# VirtualWire.net
KiCad netlist of a schematic drawn in Altium Designer
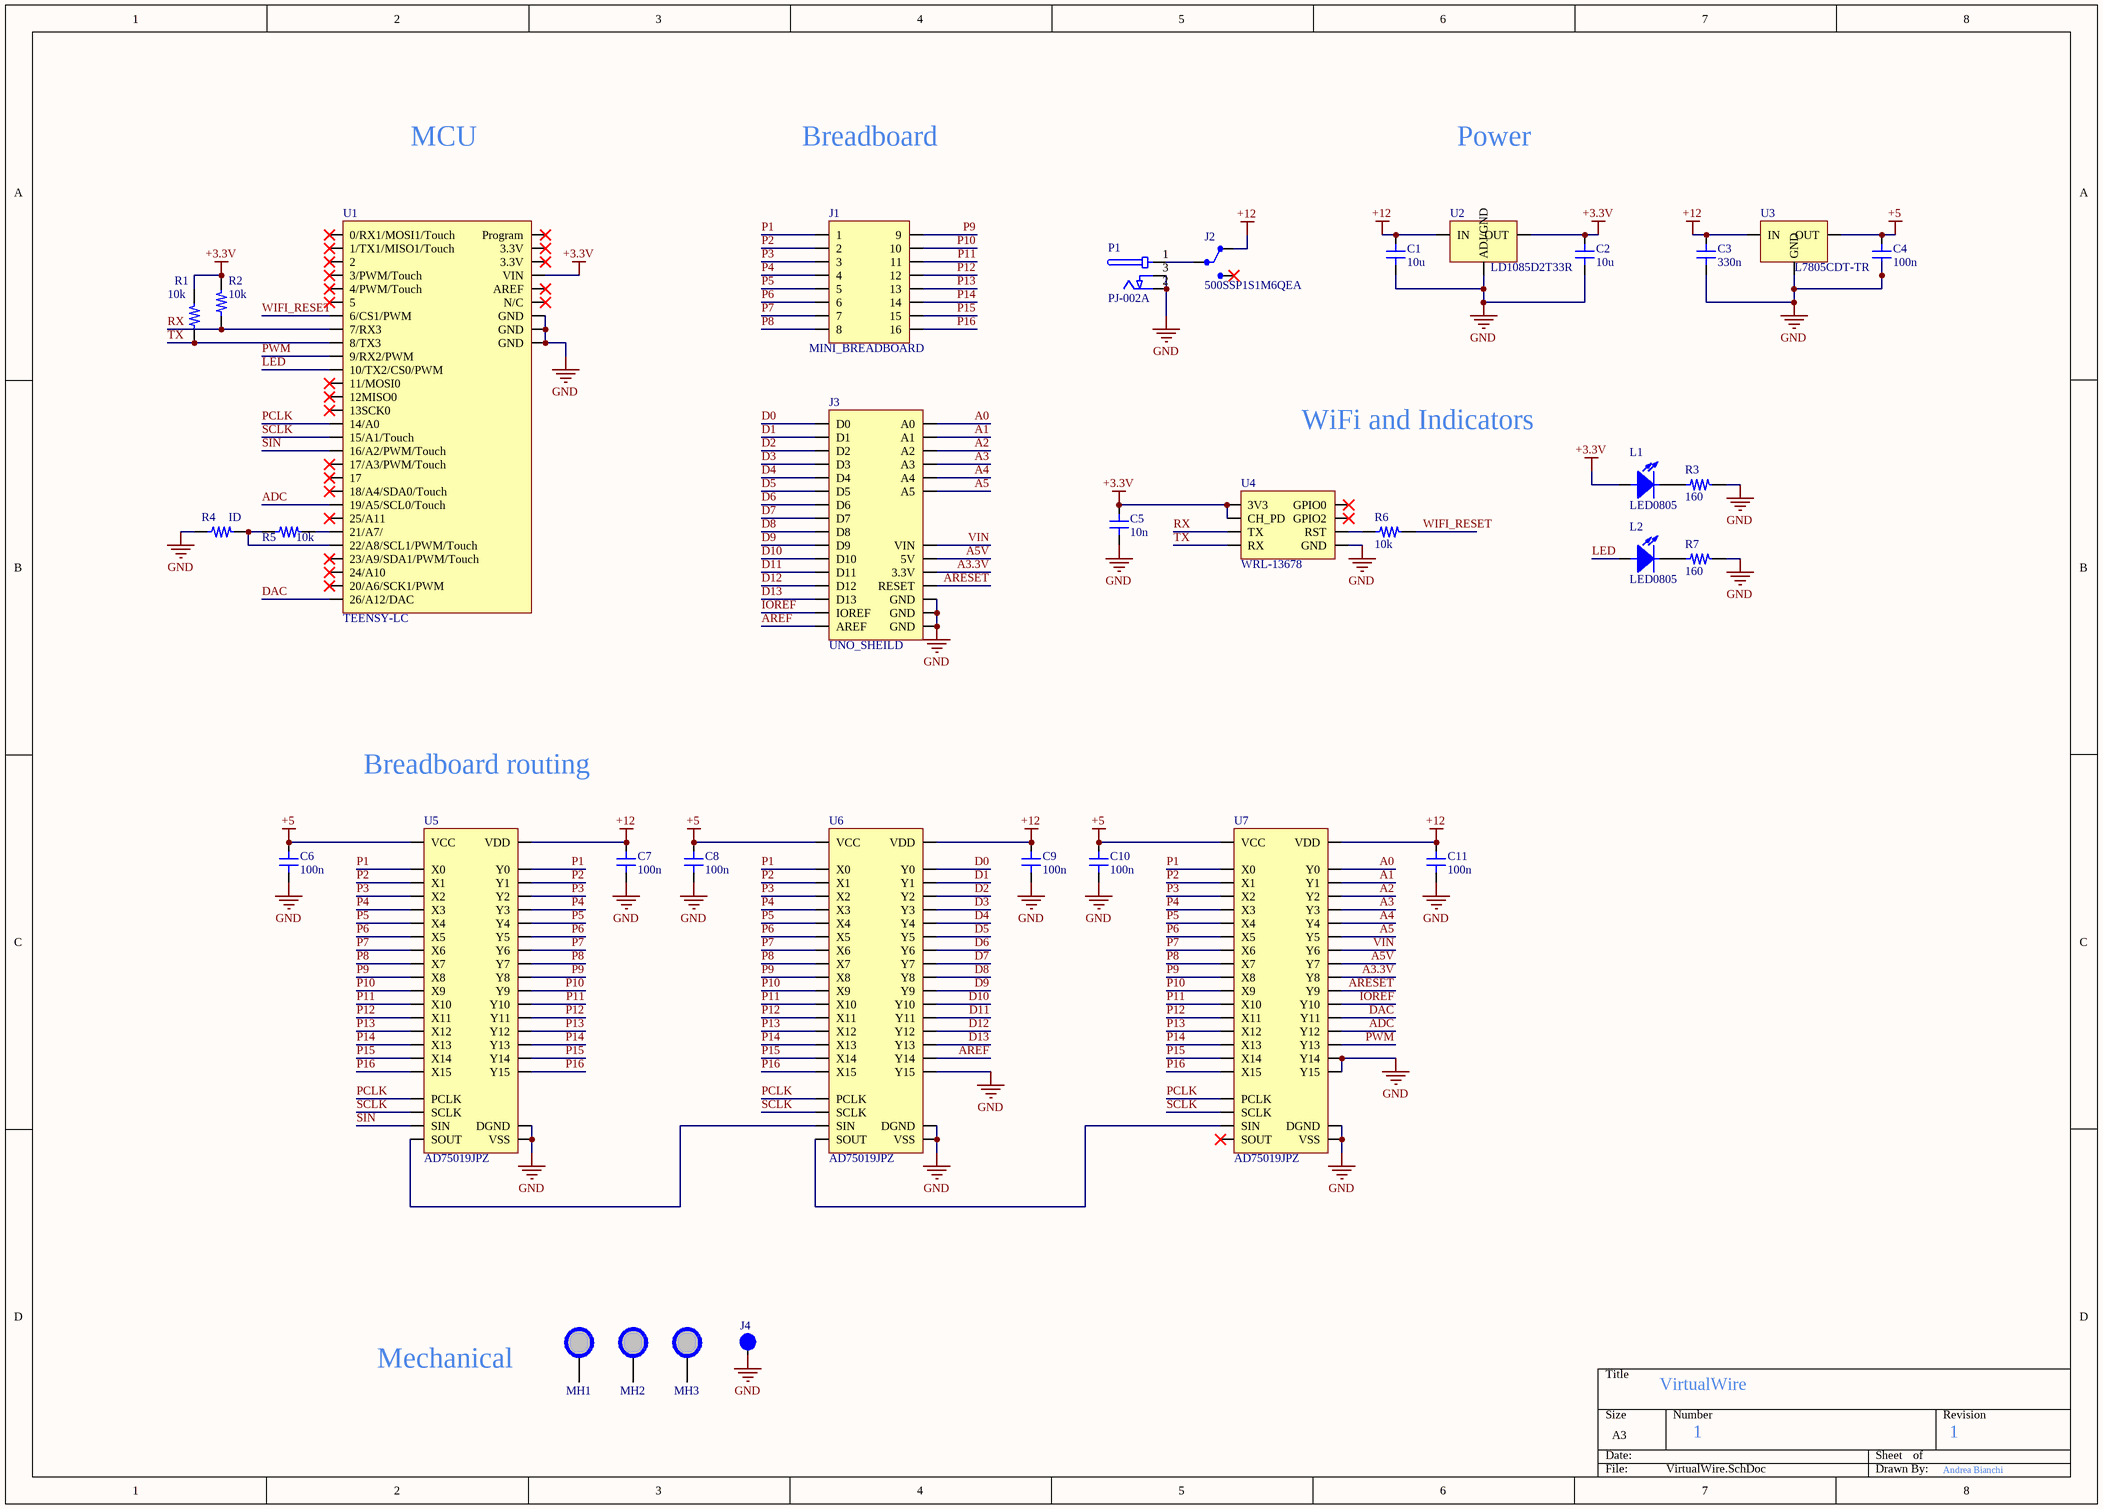
[diagram p0: VirtualWire.SchDoc]

(export (version "E")
  (design (tool "Eeschema 10.0.6"))
  (components
    (comp (ref "C1")
      (value "10u")
      (footprint "C0805")
      (description "10uF")
      (libsource (lib "VirtualWire") (part "C805_10u"))
    )
    (comp (ref "C2")
      (value "10u")
      (footprint "C0805")
      (description "10uF")
      (libsource (lib "VirtualWire") (part "C805_10u"))
    )
    (comp (ref "C3")
      (value "330n")
      (footprint "C0805")
      (description "330nF")
      (libsource (lib "VirtualWire") (part "C805_330n"))
    )
    (comp (ref "C4")
      (value "100n")
      (footprint "C0805")
      (description "100nF")
      (libsource (lib "VirtualWire") (part "C805_100n"))
    )
    (comp (ref "C5")
      (value "10n")
      (footprint "C0805")
      (description "10nF")
      (libsource (lib "VirtualWire") (part "C805_10n"))
    )
    (comp (ref "C6")
      (value "100n")
      (footprint "C0805")
      (description "100nF")
      (libsource (lib "VirtualWire") (part "C805_100n"))
    )
    (comp (ref "C7")
      (value "100n")
      (footprint "C0805")
      (description "100nF")
      (libsource (lib "VirtualWire") (part "C805_100n"))
    )
    (comp (ref "C8")
      (value "100n")
      (footprint "C0805")
      (description "100nF")
      (libsource (lib "VirtualWire") (part "C805_100n"))
    )
    (comp (ref "C9")
      (value "100n")
      (footprint "C0805")
      (description "100nF")
      (libsource (lib "VirtualWire") (part "C805_100n"))
    )
    (comp (ref "C10")
      (value "100n")
      (footprint "C0805")
      (description "100nF")
      (libsource (lib "VirtualWire") (part "C805_100n"))
    )
    (comp (ref "C11")
      (value "100n")
      (footprint "C0805")
      (description "100nF")
      (libsource (lib "VirtualWire") (part "C805_100n"))
    )
    (comp (ref "J1")
      (value "MINI_BREADBOARD")
      (footprint "MINI_BREADBOARD HOLE")
      (description "Mini Breadboard 16x2")
      (libsource (lib "VirtualWire") (part "MINI_BREADBOARD"))
    )
    (comp (ref "J2")
      (value "500SSP1S1M6QEA")
      (footprint "SLIDE SPDT")
      (description "SWITCH SLIDE SPDT 5A 120V")
      (fields (field (name "MANUFACTURER") "E-Switch"))
      (libsource (lib "VirtualWire") (part "SLIDE SPDT"))
    )
    (comp (ref "J3")
      (value "UNO_SHEILD")
      (footprint "ARDUINO_UNO_SHIELD")
      (libsource (lib "VirtualWire") (part "ARDUINO_UNO_SHIELD"))
    )
    (comp (ref "J4")
      (value "EPAD")
      (footprint "EPAD")
      (description "Exposed PAD")
      (libsource (lib "VirtualWire") (part "EPAD"))
    )
    (comp (ref "L1")
      (value "LED0805")
      (footprint "LED0805")
      (description "LED0805 any color")
      (libsource (lib "VirtualWire") (part "LED0805"))
    )
    (comp (ref "L2")
      (value "LED0805")
      (footprint "LED0805")
      (description "LED0805 any color")
      (libsource (lib "VirtualWire") (part "LED0805"))
    )
    (comp (ref "MH1")
      (value "MH 3.2mm NP")
      (footprint "MH3.2mm")
      (description "Mounting hole 3.2mm non plated")
      (libsource (lib "VirtualWire") (part "MHNP"))
    )
    (comp (ref "MH2")
      (value "MH 3.2mm NP")
      (footprint "MH3.2mm")
      (description "Mounting hole 3.2mm non plated")
      (libsource (lib "VirtualWire") (part "MHNP"))
    )
    (comp (ref "MH3")
      (value "MH 3.2mm NP")
      (footprint "MH3.2mm")
      (description "Mounting hole 3.2mm non plated")
      (libsource (lib "VirtualWire") (part "MHNP"))
    )
    (comp (ref "P1")
      (value "PJ-002A")
      (footprint "PJ-002A")
      (description "PJ-002 Series 2 x 6.5 mm 16 V Right Angle Through Hole Power Jack")
      (fields (field (name "MANUFACTURER") "CUI"))
      (libsource (lib "VirtualWire") (part "PJ-002A"))
    )
    (comp (ref "R1") (value "10k") (footprint "R0805") (libsource (lib "VirtualWire") (part "R0805_10k")))
    (comp (ref "R2") (value "10k") (footprint "R0805") (libsource (lib "VirtualWire") (part "R0805_10k")))
    (comp (ref "R3")
      (value "160")
      (footprint "R0805")
      (description "160 Ohm")
      (libsource (lib "VirtualWire") (part "R0805_160"))
    )
    (comp (ref "R4") (value "ID") (footprint "R0805") (libsource (lib "VirtualWire") (part "R0805_10k")))
    (comp (ref "R5") (value "10k") (footprint "R0805") (libsource (lib "VirtualWire") (part "R0805_10k")))
    (comp (ref "R6") (value "10k") (footprint "R0805") (libsource (lib "VirtualWire") (part "R0805_10k")))
    (comp (ref "R7")
      (value "160")
      (footprint "R0805")
      (description "160 Ohm")
      (libsource (lib "VirtualWire") (part "R0805_160"))
    )
    (comp (ref "U1")
      (value "TEENSY-LC")
      (footprint "TEENSY-LC")
      (description "DEV TEENSY LC 13305")
      (fields (field (name "MANUFACTURER") "SparkFun") (field (name "MANUFACTURER PART NUMBER") "DEV-13305"))
      (libsource (lib "VirtualWire") (part "TEENSY-LC"))
    )
    (comp (ref "U2")
      (value "LD1085D2T33R")
      (footprint "D2PAK")
      (description "Fixed LDO Voltage Regulator, 6.3V to 30V, 1.3V Dropout, 3.3Vout, 3Aout, TO-263-3")
      (fields (field (name "MANUFACTURER") "STMicroelectronics"))
      (libsource (lib "VirtualWire") (part "LD1085D2T33R"))
    )
    (comp (ref "U3")
      (value "L7805CDT-TR")
      (footprint "DPAK")
      (description "IC REG LDO 5V 1.5A DPAK")
      (fields (field (name "MANUFACTURER") "STMicroelectronics"))
      (libsource (lib "VirtualWire") (part "L7805CDT-TR"))
    )
    (comp (ref "U4")
      (value "WRL-13678")
      (footprint "ESP8266")
      (description "WIFI ESP8266 MOD WIFI TRACE ANT")
      (fields (field (name "MANUFACTURER") "SparkFun"))
      (libsource (lib "VirtualWire") (part "ESP8266"))
    )
    (comp (ref "U5")
      (value "AD75019JPZ")
      (footprint "PLCC44_DIP")
      (description "SWITCH CROSSPOINT 16X16, SMD, 75019")
      (fields (field (name "MANUFACTURER") "Analog Devices"))
      (libsource (lib "VirtualWire") (part "AD75019JPZ"))
    )
    (comp (ref "U6")
      (value "AD75019JPZ")
      (footprint "PLCC44_DIP")
      (description "SWITCH CROSSPOINT 16X16, SMD, 75019")
      (fields (field (name "MANUFACTURER") "Analog Devices"))
      (libsource (lib "VirtualWire") (part "AD75019JPZ"))
    )
    (comp (ref "U7")
      (value "AD75019JPZ")
      (footprint "PLCC44_DIP")
      (description "SWITCH CROSSPOINT 16X16, SMD, 75019")
      (fields (field (name "MANUFACTURER") "Analog Devices"))
      (libsource (lib "VirtualWire") (part "AD75019JPZ"))
    )
  )
  (nets
    (net (code "1") (name "+3.3V") (class "Default")
      (node (ref "C2") (pin "2") (pinfunction "2_2") (pintype "passive"))
      (node (ref "C5") (pin "2") (pinfunction "2_2") (pintype "passive"))
      (node (ref "L1") (pin "2") (pinfunction "A_2") (pintype "passive"))
      (node (ref "R1") (pin "2") (pinfunction "2_2") (pintype "passive"))
      (node (ref "R2") (pin "2") (pinfunction "2_2") (pintype "passive"))
      (node (ref "U1") (pin "33") (pinfunction "VIN_33") (pintype "passive"))
      (node (ref "U2") (pin "4") (pinfunction "OUT_4") (pintype "passive"))
      (node (ref "U4") (pin "2") (pinfunction "CH_PD_2") (pintype "passive"))
      (node (ref "U4") (pin "4") (pinfunction "3V3_4") (pintype "passive"))
    )
    (net (code "2") (name "+5") (class "Default")
      (node (ref "C10") (pin "2") (pinfunction "2_2") (pintype "passive"))
      (node (ref "C4") (pin "2") (pinfunction "2_2") (pintype "passive"))
      (node (ref "C6") (pin "2") (pinfunction "2_2") (pintype "passive"))
      (node (ref "C8") (pin "2") (pinfunction "2_2") (pintype "passive"))
      (node (ref "U3") (pin "3") (pinfunction "OUT_3") (pintype "passive"))
      (node (ref "U5") (pin "42") (pinfunction "VCC_42") (pintype "passive"))
      (node (ref "U6") (pin "42") (pinfunction "VCC_42") (pintype "passive"))
      (node (ref "U7") (pin "42") (pinfunction "VCC_42") (pintype "passive"))
    )
    (net (code "3") (name "+12") (class "Default")
      (node (ref "C1") (pin "2") (pinfunction "2_2") (pintype "passive"))
      (node (ref "C11") (pin "2") (pinfunction "2_2") (pintype "passive"))
      (node (ref "C3") (pin "2") (pinfunction "2_2") (pintype "passive"))
      (node (ref "C7") (pin "2") (pinfunction "2_2") (pintype "passive"))
      (node (ref "C9") (pin "2") (pinfunction "2_2") (pintype "passive"))
      (node (ref "J2") (pin "1") (pinfunction "1_1") (pintype "passive"))
      (node (ref "U2") (pin "3") (pinfunction "IN_3") (pintype "passive"))
      (node (ref "U3") (pin "1") (pinfunction "IN_1") (pintype "passive"))
      (node (ref "U5") (pin "41") (pinfunction "VDD_41") (pintype "passive"))
      (node (ref "U6") (pin "41") (pinfunction "VDD_41") (pintype "passive"))
      (node (ref "U7") (pin "41") (pinfunction "VDD_41") (pintype "passive"))
    )
    (net (code "4") (name "/A0") (class "Default")
      (node (ref "J3") (pin "22") (pinfunction "A0_22") (pintype "passive"))
      (node (ref "U7") (pin "31") (pinfunction "Y0_31") (pintype "passive"))
    )
    (net (code "5") (name "/A1") (class "Default")
      (node (ref "J3") (pin "21") (pinfunction "A1_21") (pintype "passive"))
      (node (ref "U7") (pin "32") (pinfunction "Y1_32") (pintype "passive"))
    )
    (net (code "6") (name "/A2") (class "Default")
      (node (ref "J3") (pin "20") (pinfunction "A2_20") (pintype "passive"))
      (node (ref "U7") (pin "33") (pinfunction "Y2_33") (pintype "passive"))
    )
    (net (code "7") (name "/A3") (class "Default")
      (node (ref "J3") (pin "19") (pinfunction "A3_19") (pintype "passive"))
      (node (ref "U7") (pin "34") (pinfunction "Y3_34") (pintype "passive"))
    )
    (net (code "8") (name "/A3.3V") (class "Default")
      (node (ref "J3") (pin "27") (pinfunction "3.3V_27") (pintype "passive"))
      (node (ref "U7") (pin "14") (pinfunction "Y8_14") (pintype "passive"))
    )
    (net (code "9") (name "/A4") (class "Default")
      (node (ref "J3") (pin "18") (pinfunction "A4_18") (pintype "passive"))
      (node (ref "U7") (pin "35") (pinfunction "Y4_35") (pintype "passive"))
    )
    (net (code "10") (name "/A5") (class "Default")
      (node (ref "J3") (pin "17") (pinfunction "A5_17") (pintype "passive"))
      (node (ref "U7") (pin "36") (pinfunction "Y5_36") (pintype "passive"))
    )
    (net (code "11") (name "/A5V") (class "Default")
      (node (ref "J3") (pin "26") (pinfunction "5V_26") (pintype "passive"))
      (node (ref "U7") (pin "38") (pinfunction "Y7_38") (pintype "passive"))
    )
    (net (code "12") (name "/ADC") (class "Default")
      (node (ref "U1") (pin "26") (pinfunction "19/A5/SCL0/Touch_26") (pintype "passive"))
      (node (ref "U7") (pin "10") (pinfunction "Y12_10") (pintype "passive"))
    )
    (net (code "13") (name "/AREF") (class "Default")
      (node (ref "J3") (pin "16") (pinfunction "AREF_16") (pintype "passive"))
      (node (ref "U6") (pin "8") (pinfunction "Y14_8") (pintype "passive"))
    )
    (net (code "14") (name "/ARESET") (class "Default")
      (node (ref "J3") (pin "28") (pinfunction "RESET_28") (pintype "passive"))
      (node (ref "U7") (pin "13") (pinfunction "Y9_13") (pintype "passive"))
    )
    (net (code "15") (name "/D0") (class "Default")
      (node (ref "J3") (pin "1") (pinfunction "D0_1") (pintype "passive"))
      (node (ref "U6") (pin "31") (pinfunction "Y0_31") (pintype "passive"))
    )
    (net (code "16") (name "/D1") (class "Default")
      (node (ref "J3") (pin "2") (pinfunction "D1_2") (pintype "passive"))
      (node (ref "U6") (pin "32") (pinfunction "Y1_32") (pintype "passive"))
    )
    (net (code "17") (name "/D2") (class "Default")
      (node (ref "J3") (pin "3") (pinfunction "D2_3") (pintype "passive"))
      (node (ref "U6") (pin "33") (pinfunction "Y2_33") (pintype "passive"))
    )
    (net (code "18") (name "/D3") (class "Default")
      (node (ref "J3") (pin "4") (pinfunction "D3_4") (pintype "passive"))
      (node (ref "U6") (pin "34") (pinfunction "Y3_34") (pintype "passive"))
    )
    (net (code "19") (name "/D4") (class "Default")
      (node (ref "J3") (pin "5") (pinfunction "D4_5") (pintype "passive"))
      (node (ref "U6") (pin "35") (pinfunction "Y4_35") (pintype "passive"))
    )
    (net (code "20") (name "/D5") (class "Default")
      (node (ref "J3") (pin "6") (pinfunction "D5_6") (pintype "passive"))
      (node (ref "U6") (pin "36") (pinfunction "Y5_36") (pintype "passive"))
    )
    (net (code "21") (name "/D6") (class "Default")
      (node (ref "J3") (pin "7") (pinfunction "D6_7") (pintype "passive"))
      (node (ref "U6") (pin "37") (pinfunction "Y6_37") (pintype "passive"))
    )
    (net (code "22") (name "/D7") (class "Default")
      (node (ref "J3") (pin "8") (pinfunction "D7_8") (pintype "passive"))
      (node (ref "U6") (pin "38") (pinfunction "Y7_38") (pintype "passive"))
    )
    (net (code "23") (name "/D8") (class "Default")
      (node (ref "J3") (pin "9") (pinfunction "D8_9") (pintype "passive"))
      (node (ref "U6") (pin "14") (pinfunction "Y8_14") (pintype "passive"))
    )
    (net (code "24") (name "/D9") (class "Default")
      (node (ref "J3") (pin "10") (pinfunction "D9_10") (pintype "passive"))
      (node (ref "U6") (pin "13") (pinfunction "Y9_13") (pintype "passive"))
    )
    (net (code "25") (name "/D10") (class "Default")
      (node (ref "J3") (pin "11") (pinfunction "D10_11") (pintype "passive"))
      (node (ref "U6") (pin "12") (pinfunction "Y10_12") (pintype "passive"))
    )
    (net (code "26") (name "/D11") (class "Default")
      (node (ref "J3") (pin "12") (pinfunction "D11_12") (pintype "passive"))
      (node (ref "U6") (pin "11") (pinfunction "Y11_11") (pintype "passive"))
    )
    (net (code "27") (name "/D12") (class "Default")
      (node (ref "J3") (pin "13") (pinfunction "D12_13") (pintype "passive"))
      (node (ref "U6") (pin "10") (pinfunction "Y12_10") (pintype "passive"))
    )
    (net (code "28") (name "/D13") (class "Default")
      (node (ref "J3") (pin "14") (pinfunction "D13_14") (pintype "passive"))
      (node (ref "U6") (pin "9") (pinfunction "Y13_9") (pintype "passive"))
    )
    (net (code "29") (name "/DAC") (class "Default")
      (node (ref "U1") (pin "19") (pinfunction "26/A12/DAC_19") (pintype "passive"))
      (node (ref "U7") (pin "11") (pinfunction "Y11_11") (pintype "passive"))
    )
    (net (code "30") (name "/IOREF") (class "Default")
      (node (ref "J3") (pin "29") (pinfunction "IOREF_29") (pintype "passive"))
      (node (ref "U7") (pin "12") (pinfunction "Y10_12") (pintype "passive"))
    )
    (net (code "31") (name "/LED") (class "Default")
      (node (ref "L2") (pin "2") (pinfunction "A_2") (pintype "passive"))
      (node (ref "U1") (pin "12") (pinfunction "10/TX2/CS0/PWM_12") (pintype "passive"))
    )
    (net (code "32") (name "/P1") (class "Default")
      (node (ref "J1") (pin "1") (pinfunction "1_1") (pintype "passive"))
      (node (ref "U5") (pin "15") (pinfunction "X0_15") (pintype "passive"))
      (node (ref "U5") (pin "31") (pinfunction "Y0_31") (pintype "passive"))
      (node (ref "U6") (pin "15") (pinfunction "X0_15") (pintype "passive"))
      (node (ref "U7") (pin "15") (pinfunction "X0_15") (pintype "passive"))
    )
    (net (code "33") (name "/P2") (class "Default")
      (node (ref "J1") (pin "2") (pinfunction "2_2") (pintype "passive"))
      (node (ref "U5") (pin "16") (pinfunction "X1_16") (pintype "passive"))
      (node (ref "U5") (pin "32") (pinfunction "Y1_32") (pintype "passive"))
      (node (ref "U6") (pin "16") (pinfunction "X1_16") (pintype "passive"))
      (node (ref "U7") (pin "16") (pinfunction "X1_16") (pintype "passive"))
    )
    (net (code "34") (name "/P3") (class "Default")
      (node (ref "J1") (pin "3") (pinfunction "3_3") (pintype "passive"))
      (node (ref "U5") (pin "17") (pinfunction "X2_17") (pintype "passive"))
      (node (ref "U5") (pin "33") (pinfunction "Y2_33") (pintype "passive"))
      (node (ref "U6") (pin "17") (pinfunction "X2_17") (pintype "passive"))
      (node (ref "U7") (pin "17") (pinfunction "X2_17") (pintype "passive"))
    )
    (net (code "35") (name "/P4") (class "Default")
      (node (ref "J1") (pin "4") (pinfunction "4_4") (pintype "passive"))
      (node (ref "U5") (pin "18") (pinfunction "X3_18") (pintype "passive"))
      (node (ref "U5") (pin "34") (pinfunction "Y3_34") (pintype "passive"))
      (node (ref "U6") (pin "18") (pinfunction "X3_18") (pintype "passive"))
      (node (ref "U7") (pin "18") (pinfunction "X3_18") (pintype "passive"))
    )
    (net (code "36") (name "/P5") (class "Default")
      (node (ref "J1") (pin "5") (pinfunction "5_5") (pintype "passive"))
      (node (ref "U5") (pin "19") (pinfunction "X4_19") (pintype "passive"))
      (node (ref "U5") (pin "35") (pinfunction "Y4_35") (pintype "passive"))
      (node (ref "U6") (pin "19") (pinfunction "X4_19") (pintype "passive"))
      (node (ref "U7") (pin "19") (pinfunction "X4_19") (pintype "passive"))
    )
    (net (code "37") (name "/P6") (class "Default")
      (node (ref "J1") (pin "6") (pinfunction "6_6") (pintype "passive"))
      (node (ref "U5") (pin "20") (pinfunction "X5_20") (pintype "passive"))
      (node (ref "U5") (pin "36") (pinfunction "Y5_36") (pintype "passive"))
      (node (ref "U6") (pin "20") (pinfunction "X5_20") (pintype "passive"))
      (node (ref "U7") (pin "20") (pinfunction "X5_20") (pintype "passive"))
    )
    (net (code "38") (name "/P7") (class "Default")
      (node (ref "J1") (pin "7") (pinfunction "7_7") (pintype "passive"))
      (node (ref "U5") (pin "21") (pinfunction "X6_21") (pintype "passive"))
      (node (ref "U5") (pin "37") (pinfunction "Y6_37") (pintype "passive"))
      (node (ref "U6") (pin "21") (pinfunction "X6_21") (pintype "passive"))
      (node (ref "U7") (pin "21") (pinfunction "X6_21") (pintype "passive"))
    )
    (net (code "39") (name "/P8") (class "Default")
      (node (ref "J1") (pin "8") (pinfunction "8_8") (pintype "passive"))
      (node (ref "U5") (pin "22") (pinfunction "X7_22") (pintype "passive"))
      (node (ref "U5") (pin "38") (pinfunction "Y7_38") (pintype "passive"))
      (node (ref "U6") (pin "22") (pinfunction "X7_22") (pintype "passive"))
      (node (ref "U7") (pin "22") (pinfunction "X7_22") (pintype "passive"))
    )
    (net (code "40") (name "/P9") (class "Default")
      (node (ref "J1") (pin "9") (pinfunction "9_9") (pintype "passive"))
      (node (ref "U5") (pin "14") (pinfunction "Y8_14") (pintype "passive"))
      (node (ref "U5") (pin "23") (pinfunction "X8_23") (pintype "passive"))
      (node (ref "U6") (pin "23") (pinfunction "X8_23") (pintype "passive"))
      (node (ref "U7") (pin "23") (pinfunction "X8_23") (pintype "passive"))
    )
    (net (code "41") (name "/P10") (class "Default")
      (node (ref "J1") (pin "10") (pinfunction "10_10") (pintype "passive"))
      (node (ref "U5") (pin "13") (pinfunction "Y9_13") (pintype "passive"))
      (node (ref "U5") (pin "24") (pinfunction "X9_24") (pintype "passive"))
      (node (ref "U6") (pin "24") (pinfunction "X9_24") (pintype "passive"))
      (node (ref "U7") (pin "24") (pinfunction "X9_24") (pintype "passive"))
    )
    (net (code "42") (name "/P11") (class "Default")
      (node (ref "J1") (pin "11") (pinfunction "11_11") (pintype "passive"))
      (node (ref "U5") (pin "12") (pinfunction "Y10_12") (pintype "passive"))
      (node (ref "U5") (pin "25") (pinfunction "X10_25") (pintype "passive"))
      (node (ref "U6") (pin "25") (pinfunction "X10_25") (pintype "passive"))
      (node (ref "U7") (pin "25") (pinfunction "X10_25") (pintype "passive"))
    )
    (net (code "43") (name "/P12") (class "Default")
      (node (ref "J1") (pin "12") (pinfunction "12_12") (pintype "passive"))
      (node (ref "U5") (pin "11") (pinfunction "Y11_11") (pintype "passive"))
      (node (ref "U5") (pin "26") (pinfunction "X11_26") (pintype "passive"))
      (node (ref "U6") (pin "26") (pinfunction "X11_26") (pintype "passive"))
      (node (ref "U7") (pin "26") (pinfunction "X11_26") (pintype "passive"))
    )
    (net (code "44") (name "/P13") (class "Default")
      (node (ref "J1") (pin "13") (pinfunction "13_13") (pintype "passive"))
      (node (ref "U5") (pin "10") (pinfunction "Y12_10") (pintype "passive"))
      (node (ref "U5") (pin "27") (pinfunction "X12_27") (pintype "passive"))
      (node (ref "U6") (pin "27") (pinfunction "X12_27") (pintype "passive"))
      (node (ref "U7") (pin "27") (pinfunction "X12_27") (pintype "passive"))
    )
    (net (code "45") (name "/P14") (class "Default")
      (node (ref "J1") (pin "14") (pinfunction "14_14") (pintype "passive"))
      (node (ref "U5") (pin "28") (pinfunction "X13_28") (pintype "passive"))
      (node (ref "U5") (pin "9") (pinfunction "Y13_9") (pintype "passive"))
      (node (ref "U6") (pin "28") (pinfunction "X13_28") (pintype "passive"))
      (node (ref "U7") (pin "28") (pinfunction "X13_28") (pintype "passive"))
    )
    (net (code "46") (name "/P15") (class "Default")
      (node (ref "J1") (pin "15") (pinfunction "15_15") (pintype "passive"))
      (node (ref "U5") (pin "29") (pinfunction "X14_29") (pintype "passive"))
      (node (ref "U5") (pin "8") (pinfunction "Y14_8") (pintype "passive"))
      (node (ref "U6") (pin "29") (pinfunction "X14_29") (pintype "passive"))
      (node (ref "U7") (pin "29") (pinfunction "X14_29") (pintype "passive"))
    )
    (net (code "47") (name "/P16") (class "Default")
      (node (ref "J1") (pin "16") (pinfunction "16_16") (pintype "passive"))
      (node (ref "U5") (pin "30") (pinfunction "X15_30") (pintype "passive"))
      (node (ref "U5") (pin "7") (pinfunction "Y15_7") (pintype "passive"))
      (node (ref "U6") (pin "30") (pinfunction "X15_30") (pintype "passive"))
      (node (ref "U7") (pin "30") (pinfunction "X15_30") (pintype "passive"))
    )
    (net (code "48") (name "/PCLK") (class "Default")
      (node (ref "U1") (pin "21") (pinfunction "14/A0_21") (pintype "passive"))
      (node (ref "U5") (pin "1") (pinfunction "PCLK_1") (pintype "passive"))
      (node (ref "U6") (pin "1") (pinfunction "PCLK_1") (pintype "passive"))
      (node (ref "U7") (pin "1") (pinfunction "PCLK_1") (pintype "passive"))
    )
    (net (code "49") (name "/PWM") (class "Default")
      (node (ref "U1") (pin "11") (pinfunction "9/RX2/PWM_11") (pintype "passive"))
      (node (ref "U7") (pin "9") (pinfunction "Y13_9") (pintype "passive"))
    )
    (net (code "50") (name "/RX") (class "Default")
      (node (ref "R2") (pin "1") (pinfunction "1_1") (pintype "passive"))
      (node (ref "U1") (pin "9") (pinfunction "7/RX3_9") (pintype "passive"))
      (node (ref "U4") (pin "1") (pinfunction "TX_1") (pintype "passive"))
    )
    (net (code "51") (name "/SCLK") (class "Default")
      (node (ref "U1") (pin "22") (pinfunction "15/A1/Touch_22") (pintype "passive"))
      (node (ref "U5") (pin "2") (pinfunction "SCLK_2") (pintype "passive"))
      (node (ref "U6") (pin "2") (pinfunction "SCLK_2") (pintype "passive"))
      (node (ref "U7") (pin "2") (pinfunction "SCLK_2") (pintype "passive"))
    )
    (net (code "52") (name "/SIN") (class "Default")
      (node (ref "U1") (pin "23") (pinfunction "16/A2/PWM/Touch_23") (pintype "passive"))
      (node (ref "U5") (pin "3") (pinfunction "SIN_3") (pintype "passive"))
    )
    (net (code "53") (name "/TX") (class "Default")
      (node (ref "R1") (pin "1") (pinfunction "1_1") (pintype "passive"))
      (node (ref "U1") (pin "10") (pinfunction "8/TX3_10") (pintype "passive"))
      (node (ref "U4") (pin "5") (pinfunction "RX_5") (pintype "passive"))
    )
    (net (code "54") (name "/VIN") (class "Default")
      (node (ref "J3") (pin "23") (pinfunction "VIN_23") (pintype "passive"))
      (node (ref "U7") (pin "37") (pinfunction "Y6_37") (pintype "passive"))
    )
    (net (code "55") (name "/WIFI_RESET") (class "Default")
      (node (ref "R6") (pin "2") (pinfunction "2_2") (pintype "passive"))
      (node (ref "U1") (pin "8") (pinfunction "6/CS1/PWM_8") (pintype "passive"))
    )
    (net (code "56") (name "GND") (class "Default")
      (node (ref "C1") (pin "1") (pinfunction "1_1") (pintype "passive"))
      (node (ref "C10") (pin "1") (pinfunction "1_1") (pintype "passive"))
      (node (ref "C11") (pin "1") (pinfunction "1_1") (pintype "passive"))
      (node (ref "C2") (pin "1") (pinfunction "1_1") (pintype "passive"))
      (node (ref "C3") (pin "1") (pinfunction "1_1") (pintype "passive"))
      (node (ref "C4") (pin "1") (pinfunction "1_1") (pintype "passive"))
      (node (ref "C5") (pin "1") (pinfunction "1_1") (pintype "passive"))
      (node (ref "C6") (pin "1") (pinfunction "1_1") (pintype "passive"))
      (node (ref "C7") (pin "1") (pinfunction "1_1") (pintype "passive"))
      (node (ref "C8") (pin "1") (pinfunction "1_1") (pintype "passive"))
      (node (ref "C9") (pin "1") (pinfunction "1_1") (pintype "passive"))
      (node (ref "J3") (pin "15") (pinfunction "GND_15") (pintype "passive"))
      (node (ref "J3") (pin "24") (pinfunction "GND_24") (pintype "passive"))
      (node (ref "J3") (pin "25") (pinfunction "GND_25") (pintype "passive"))
      (node (ref "J4") (pin "1") (pinfunction "1_1") (pintype "passive"))
      (node (ref "P1") (pin "2") (pinfunction "3_2") (pintype "passive"))
      (node (ref "P1") (pin "3") (pinfunction "2_3") (pintype "passive"))
      (node (ref "R3") (pin "2") (pinfunction "2_2") (pintype "passive"))
      (node (ref "R4") (pin "1") (pinfunction "1_1") (pintype "passive"))
      (node (ref "R7") (pin "2") (pinfunction "2_2") (pintype "passive"))
      (node (ref "U1") (pin "1") (pinfunction "GND_1") (pintype "passive"))
      (node (ref "U1") (pin "17") (pinfunction "GND_17") (pintype "passive"))
      (node (ref "U1") (pin "32") (pinfunction "GND_32") (pintype "passive"))
      (node (ref "U2") (pin "1") (pinfunction "ADJ/GND_1") (pintype "passive"))
      (node (ref "U3") (pin "4") (pinfunction "GND_4") (pintype "passive"))
      (node (ref "U4") (pin "8") (pinfunction "GND_8") (pintype "passive"))
      (node (ref "U5") (pin "4") (pinfunction "VSS_4") (pintype "passive"))
      (node (ref "U5") (pin "43") (pinfunction "DGND_43") (pintype "passive"))
      (node (ref "U6") (pin "4") (pinfunction "VSS_4") (pintype "passive"))
      (node (ref "U6") (pin "43") (pinfunction "DGND_43") (pintype "passive"))
      (node (ref "U6") (pin "7") (pinfunction "Y15_7") (pintype "passive"))
      (node (ref "U7") (pin "4") (pinfunction "VSS_4") (pintype "passive"))
      (node (ref "U7") (pin "43") (pinfunction "DGND_43") (pintype "passive"))
      (node (ref "U7") (pin "7") (pinfunction "Y15_7") (pintype "passive"))
      (node (ref "U7") (pin "8") (pinfunction "Y14_8") (pintype "passive"))
    )
    (net (code "57") (name "Net-(J2-Pad2)") (class "Default")
      (node (ref "J2") (pin "2") (pinfunction "2_2") (pintype "passive"))
      (node (ref "P1") (pin "1") (pinfunction "1_1") (pintype "passive"))
    )
    (net (code "58") (name "Net-(L1-C)") (class "Default")
      (node (ref "L1") (pin "1") (pinfunction "C_1") (pintype "passive"))
      (node (ref "R3") (pin "1") (pinfunction "1_1") (pintype "passive"))
    )
    (net (code "59") (name "Net-(L2-C)") (class "Default")
      (node (ref "L2") (pin "1") (pinfunction "C_1") (pintype "passive"))
      (node (ref "R7") (pin "1") (pinfunction "1_1") (pintype "passive"))
    )
    (net (code "60") (name "Net-(U1-21{slash}A7{slash})") (class "Default")
      (node (ref "R5") (pin "2") (pinfunction "2_2") (pintype "passive"))
      (node (ref "U1") (pin "28") (pinfunction "21/A7/_28") (pintype "passive"))
    )
    (net (code "61") (name "Net-(U1-22{slash}A8{slash}SCL1{slash}PWM{slash}Touch)") (class "Default")
      (node (ref "R4") (pin "2") (pinfunction "2_2") (pintype "passive"))
      (node (ref "R5") (pin "1") (pinfunction "1_1") (pintype "passive"))
      (node (ref "U1") (pin "29") (pinfunction "22/A8/SCL1/PWM/Touch_29") (pintype "passive"))
    )
    (net (code "62") (name "Net-(U4-RST)") (class "Default")
      (node (ref "R6") (pin "1") (pinfunction "1_1") (pintype "passive"))
      (node (ref "U4") (pin "3") (pinfunction "RST_3") (pintype "passive"))
    )
    (net (code "63") (name "Net-(U5-SOUT)") (class "Default")
      (node (ref "U5") (pin "44") (pinfunction "SOUT_44") (pintype "passive"))
      (node (ref "U6") (pin "3") (pinfunction "SIN_3") (pintype "passive"))
    )
    (net (code "64") (name "Net-(U6-SOUT)") (class "Default")
      (node (ref "U6") (pin "44") (pinfunction "SOUT_44") (pintype "passive"))
      (node (ref "U7") (pin "3") (pinfunction "SIN_3") (pintype "passive"))
    )
    (net (code "65") (name "unconnected-(J2-Pad3)") (class "Default")
      (node (ref "J2") (pin "3") (pinfunction "3_3") (pintype "passive+no_connect"))
    )
    (net (code "66") (name "unconnected-(MH1-Pad1)") (class "Default")
      (node (ref "MH1") (pin "1") (pinfunction "1_1") (pintype "passive"))
    )
    (net (code "67") (name "unconnected-(MH2-Pad1)") (class "Default")
      (node (ref "MH2") (pin "1") (pinfunction "1_1") (pintype "passive"))
    )
    (net (code "68") (name "unconnected-(MH3-Pad1)") (class "Default")
      (node (ref "MH3") (pin "1") (pinfunction "1_1") (pintype "passive"))
    )
    (net (code "69") (name "unconnected-(U1-0{slash}RX1{slash}MOSI1{slash}Touch-Pad2)") (class "Default")
      (node (ref "U1") (pin "2") (pinfunction "0/RX1/MOSI1/Touch_2") (pintype "passive+no_connect"))
    )
    (net (code "70") (name "unconnected-(U1-1{slash}TX1{slash}MISO1{slash}Touch-Pad3)") (class "Default")
      (node (ref "U1") (pin "3") (pinfunction "1/TX1/MISO1/Touch_3") (pintype "passive+no_connect"))
    )
    (net (code "71") (name "unconnected-(U1-2-Pad4)") (class "Default")
      (node (ref "U1") (pin "4") (pinfunction "2_4") (pintype "passive+no_connect"))
    )
    (net (code "72") (name "unconnected-(U1-3.3V-Pad16)") (class "Default")
      (node (ref "U1") (pin "16") (pinfunction "3.3V_16") (pintype "passive+no_connect"))
    )
    (net (code "73") (name "unconnected-(U1-3.3V-Pad31)") (class "Default")
      (node (ref "U1") (pin "31") (pinfunction "3.3V_31") (pintype "passive+no_connect"))
    )
    (net (code "74") (name "unconnected-(U1-3{slash}PWM{slash}Touch-Pad5)") (class "Default")
      (node (ref "U1") (pin "5") (pinfunction "3/PWM/Touch_5") (pintype "passive+no_connect"))
    )
    (net (code "75") (name "unconnected-(U1-4{slash}PWM{slash}Touch-Pad6)") (class "Default")
      (node (ref "U1") (pin "6") (pinfunction "4/PWM/Touch_6") (pintype "passive+no_connect"))
    )
    (net (code "76") (name "unconnected-(U1-5-Pad7)") (class "Default")
      (node (ref "U1") (pin "7") (pinfunction "5_7") (pintype "passive+no_connect"))
    )
    (net (code "77") (name "unconnected-(U1-11{slash}MOSI0-Pad13)") (class "Default")
      (node (ref "U1") (pin "13") (pinfunction "11/MOSI0_13") (pintype "passive+no_connect"))
    )
    (net (code "78") (name "unconnected-(U1-12MISO0-Pad14)") (class "Default")
      (node (ref "U1") (pin "14") (pinfunction "12MISO0_14") (pintype "passive+no_connect"))
    )
    (net (code "79") (name "unconnected-(U1-13SCK0-Pad20)") (class "Default")
      (node (ref "U1") (pin "20") (pinfunction "13SCK0_20") (pintype "passive+no_connect"))
    )
    (net (code "80") (name "unconnected-(U1-17-Pad15)") (class "Default")
      (node (ref "U1") (pin "15") (pinfunction "17_15") (pintype "passive+no_connect"))
    )
    (net (code "81") (name "unconnected-(U1-17{slash}A3{slash}PWM{slash}Touch-Pad24)") (class "Default")
      (node (ref "U1") (pin "24") (pinfunction "17/A3/PWM/Touch_24") (pintype "passive+no_connect"))
    )
    (net (code "82") (name "unconnected-(U1-18{slash}A4{slash}SDA0{slash}Touch-Pad25)") (class "Default")
      (node (ref "U1") (pin "25") (pinfunction "18/A4/SDA0/Touch_25") (pintype "passive+no_connect"))
    )
    (net (code "83") (name "unconnected-(U1-20{slash}A6{slash}SCK1{slash}PWM-Pad27)") (class "Default")
      (node (ref "U1") (pin "27") (pinfunction "20/A6/SCK1/PWM_27") (pintype "passive+no_connect"))
    )
    (net (code "84") (name "unconnected-(U1-23{slash}A9{slash}SDA1{slash}PWM{slash}Touch-Pad30)") (class "Default")
      (node (ref "U1") (pin "30") (pinfunction "23/A9/SDA1/PWM/Touch_30") (pintype "passive+no_connect"))
    )
    (net (code "85") (name "unconnected-(U1-24{slash}A10-Pad36)") (class "Default")
      (node (ref "U1") (pin "36") (pinfunction "24/A10_36") (pintype "passive+no_connect"))
    )
    (net (code "86") (name "unconnected-(U1-25{slash}A11-Pad37)") (class "Default")
      (node (ref "U1") (pin "37") (pinfunction "25/A11_37") (pintype "passive+no_connect"))
    )
    (net (code "87") (name "unconnected-(U1-AREF-Pad35)") (class "Default")
      (node (ref "U1") (pin "35") (pinfunction "AREF_35") (pintype "passive+no_connect"))
    )
    (net (code "88") (name "unconnected-(U1-N{slash}C-Pad34)") (class "Default")
      (node (ref "U1") (pin "34") (pinfunction "N/C_34") (pintype "passive+no_connect"))
    )
    (net (code "89") (name "unconnected-(U1-Program-Pad18)") (class "Default")
      (node (ref "U1") (pin "18") (pinfunction "Program_18") (pintype "passive+no_connect"))
    )
    (net (code "90") (name "unconnected-(U4-GPIO0-Pad6)") (class "Default")
      (node (ref "U4") (pin "6") (pinfunction "GPIO0_6") (pintype "passive+no_connect"))
    )
    (net (code "91") (name "unconnected-(U4-GPIO2-Pad7)") (class "Default")
      (node (ref "U4") (pin "7") (pinfunction "GPIO2_7") (pintype "passive+no_connect"))
    )
    (net (code "92") (name "unconnected-(U5-NC-Pad5)") (class "Default")
      (node (ref "U5") (pin "5") (pinfunction "NC_5") (pintype "passive"))
    )
    (net (code "93") (name "unconnected-(U5-NC-Pad6)") (class "Default")
      (node (ref "U5") (pin "6") (pinfunction "NC_6") (pintype "passive"))
    )
    (net (code "94") (name "unconnected-(U5-NC-Pad39)") (class "Default")
      (node (ref "U5") (pin "39") (pinfunction "NC_39") (pintype "passive"))
    )
    (net (code "95") (name "unconnected-(U5-NC-Pad40)") (class "Default")
      (node (ref "U5") (pin "40") (pinfunction "NC_40") (pintype "passive"))
    )
    (net (code "96") (name "unconnected-(U6-NC-Pad5)") (class "Default")
      (node (ref "U6") (pin "5") (pinfunction "NC_5") (pintype "passive"))
    )
    (net (code "97") (name "unconnected-(U6-NC-Pad6)") (class "Default")
      (node (ref "U6") (pin "6") (pinfunction "NC_6") (pintype "passive"))
    )
    (net (code "98") (name "unconnected-(U6-NC-Pad39)") (class "Default")
      (node (ref "U6") (pin "39") (pinfunction "NC_39") (pintype "passive"))
    )
    (net (code "99") (name "unconnected-(U6-NC-Pad40)") (class "Default")
      (node (ref "U6") (pin "40") (pinfunction "NC_40") (pintype "passive"))
    )
    (net (code "100") (name "unconnected-(U7-NC-Pad5)") (class "Default")
      (node (ref "U7") (pin "5") (pinfunction "NC_5") (pintype "passive"))
    )
    (net (code "101") (name "unconnected-(U7-NC-Pad6)") (class "Default")
      (node (ref "U7") (pin "6") (pinfunction "NC_6") (pintype "passive"))
    )
    (net (code "102") (name "unconnected-(U7-NC-Pad39)") (class "Default")
      (node (ref "U7") (pin "39") (pinfunction "NC_39") (pintype "passive"))
    )
    (net (code "103") (name "unconnected-(U7-NC-Pad40)") (class "Default")
      (node (ref "U7") (pin "40") (pinfunction "NC_40") (pintype "passive"))
    )
    (net (code "104") (name "unconnected-(U7-SOUT-Pad44)") (class "Default")
      (node (ref "U7") (pin "44") (pinfunction "SOUT_44") (pintype "passive+no_connect"))
    )
  )
)
